# DMI.net
KiCad netlist of a schematic drawn in Altium Designer
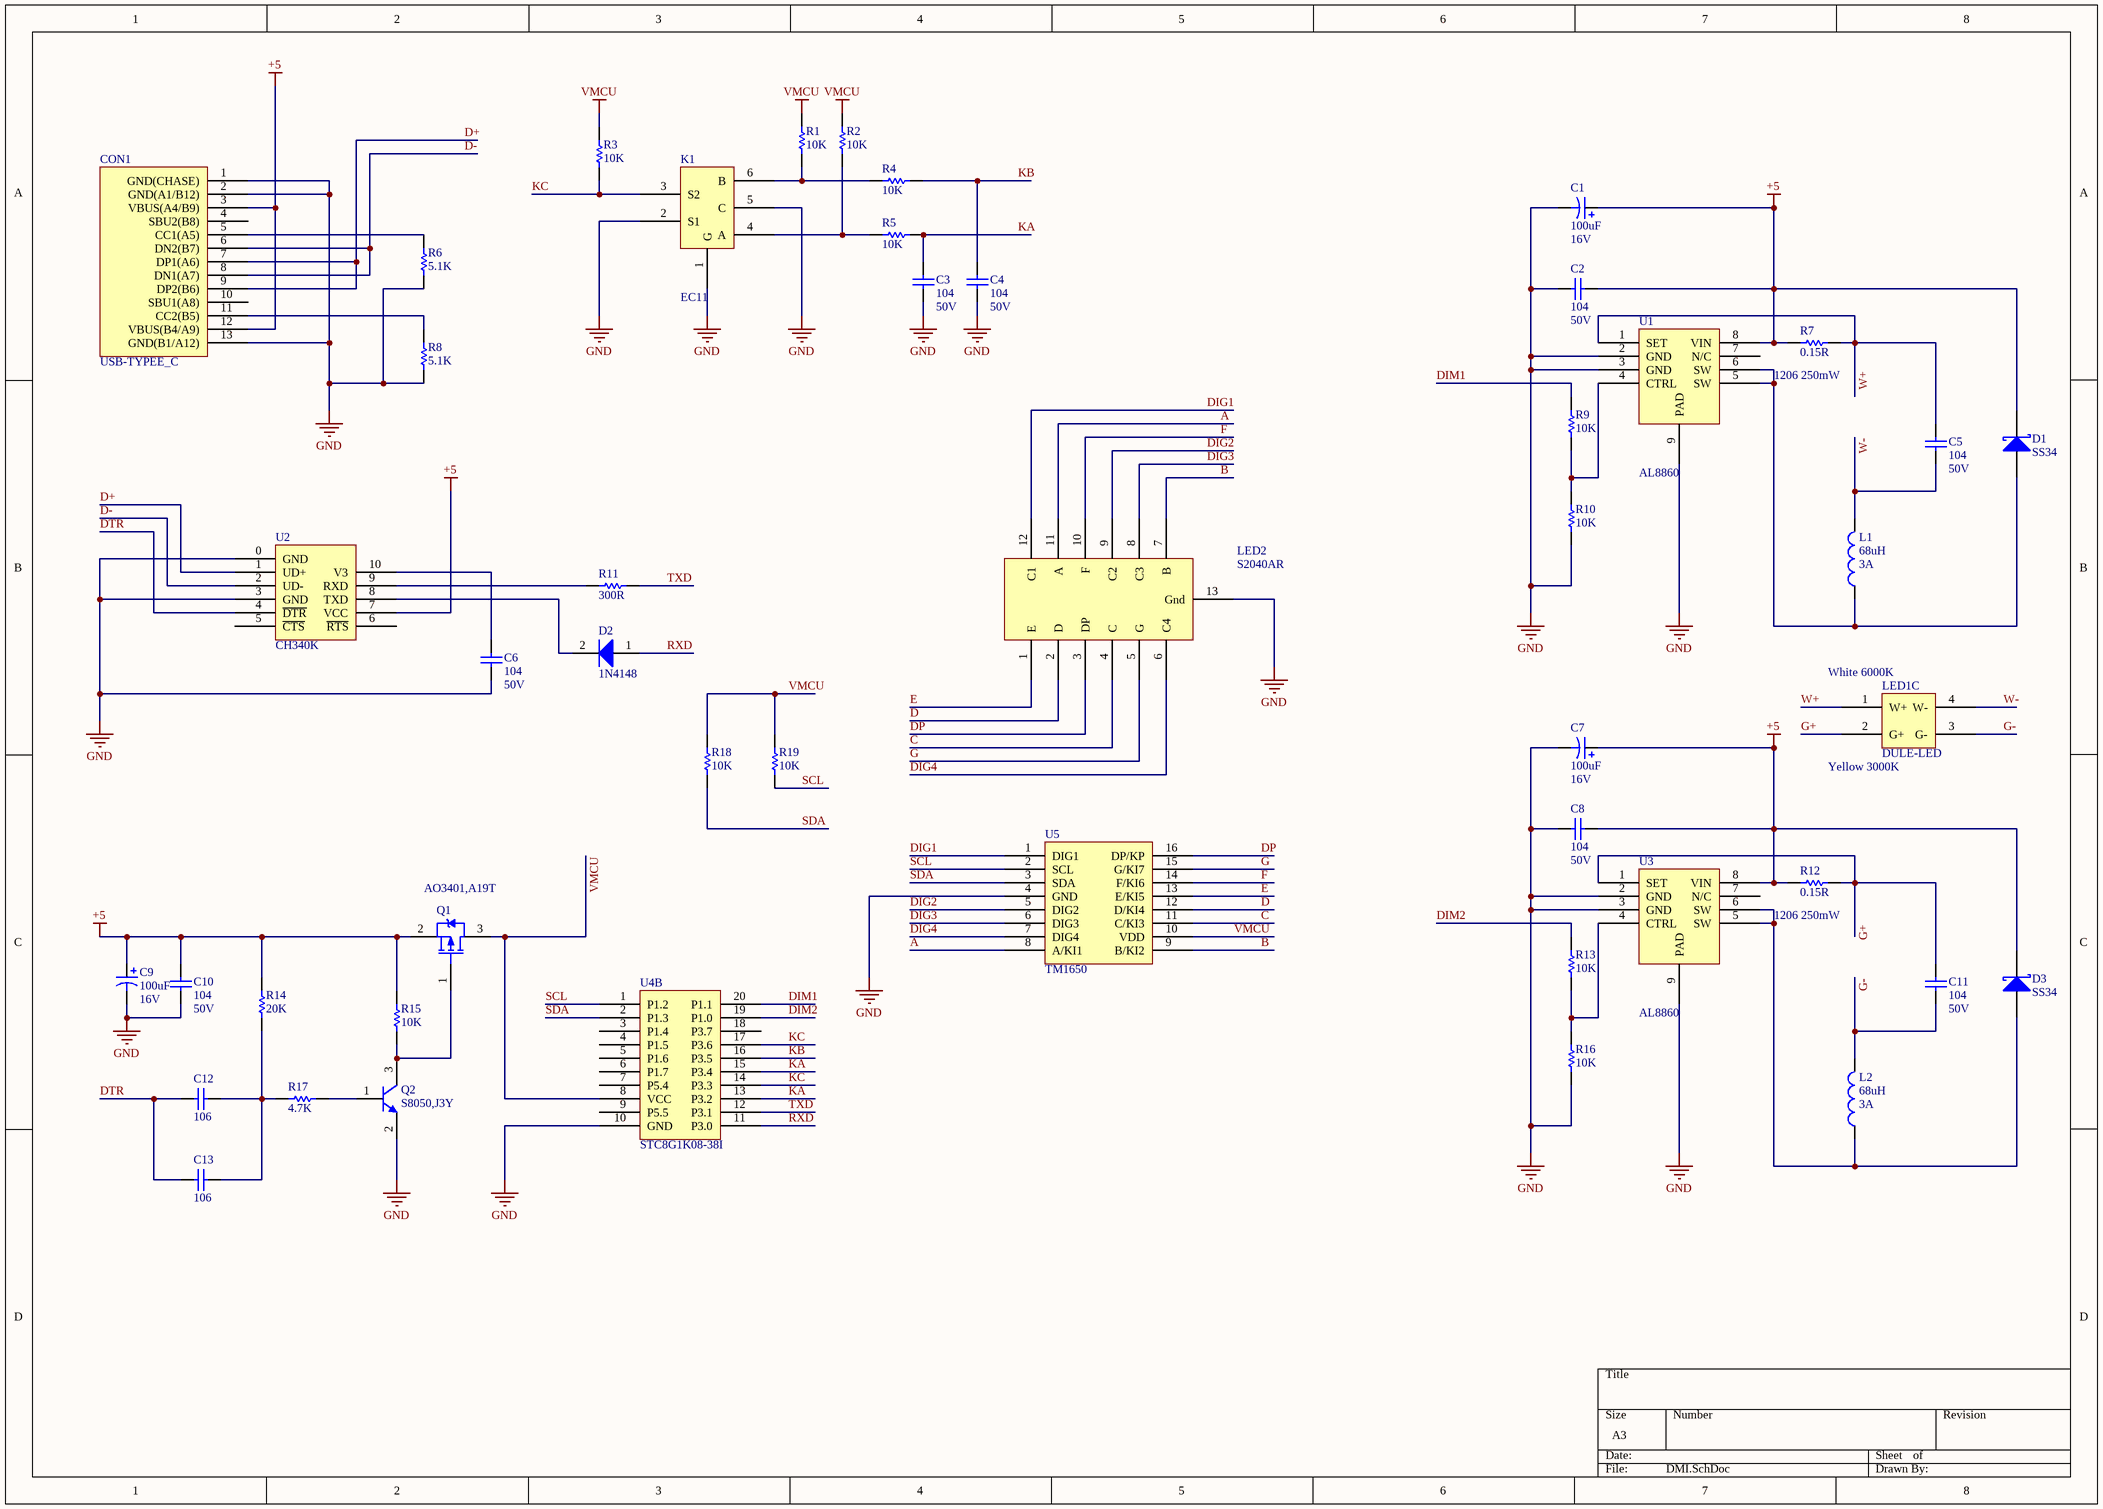
[diagram p0: DMI.SchDoc]

(export (version "E")
  (design (tool "Eeschema 10.0.6"))
  (components
    (comp (ref "C1")
      (value "16V")
      (footprint "DMI:TC6032-2412")
      (description "Polarized Capacitor (Radial)")
      (fields (field (name "ALTIUM_VALUE") "100uF") (field (name "PUBLISHER") "Altium Limited"))
      (libsource (lib "Miscellaneous Devices") (part "Cap Pol1"))
    )
    (comp (ref "C2")
      (value "50V")
      (footprint "DMI:CAPC1608L")
      (description "Capacitor")
      (fields (field (name "ALTIUM_VALUE") "104") (field (name "PUBLISHER") "Altium Limited"))
      (libsource (lib "Miscellaneous Devices") (part "Cap"))
    )
    (comp (ref "C3")
      (value "50V")
      (footprint "DMI:CAPC1608L")
      (description "Capacitor")
      (fields (field (name "ALTIUM_VALUE") "104") (field (name "PUBLISHER") "Altium Limited"))
      (libsource (lib "Miscellaneous Devices") (part "Cap"))
    )
    (comp (ref "C4")
      (value "50V")
      (footprint "DMI:CAPC1608L")
      (description "Capacitor")
      (fields (field (name "ALTIUM_VALUE") "104") (field (name "PUBLISHER") "Altium Limited"))
      (libsource (lib "Miscellaneous Devices") (part "Cap"))
    )
    (comp (ref "C5")
      (value "50V")
      (footprint "DMI:CAPC1608L")
      (description "Capacitor")
      (fields (field (name "ALTIUM_VALUE") "104") (field (name "PUBLISHER") "Altium Limited"))
      (libsource (lib "Miscellaneous Devices") (part "Cap"))
    )
    (comp (ref "C6")
      (value "50V")
      (footprint "DMI:CAPC1608L")
      (description "Capacitor")
      (fields (field (name "ALTIUM_VALUE") "104") (field (name "PUBLISHER") "Altium Limited"))
      (libsource (lib "Miscellaneous Devices") (part "Cap"))
    )
    (comp (ref "C7")
      (value "16V")
      (footprint "DMI:TC6032-2412")
      (description "Polarized Capacitor (Radial)")
      (fields (field (name "ALTIUM_VALUE") "100uF") (field (name "PUBLISHER") "Altium Limited"))
      (libsource (lib "Miscellaneous Devices") (part "Cap Pol1"))
    )
    (comp (ref "C8")
      (value "50V")
      (footprint "DMI:CAPC1608L")
      (description "Capacitor")
      (fields (field (name "ALTIUM_VALUE") "104") (field (name "PUBLISHER") "Altium Limited"))
      (libsource (lib "Miscellaneous Devices") (part "Cap"))
    )
    (comp (ref "C9")
      (value "16V")
      (footprint "DMI:TC6032-2412")
      (description "Polarized Capacitor (Radial)")
      (fields (field (name "ALTIUM_VALUE") "100uF") (field (name "PUBLISHER") "Altium Limited"))
      (libsource (lib "Miscellaneous Devices") (part "Cap Pol1"))
    )
    (comp (ref "C10")
      (value "50V")
      (footprint "DMI:CAPC1608L")
      (description "Capacitor")
      (fields (field (name "ALTIUM_VALUE") "104") (field (name "PUBLISHER") "Altium Limited"))
      (libsource (lib "Miscellaneous Devices") (part "Cap"))
    )
    (comp (ref "C11")
      (value "50V")
      (footprint "DMI:CAPC1608L")
      (description "Capacitor")
      (fields (field (name "ALTIUM_VALUE") "104") (field (name "PUBLISHER") "Altium Limited"))
      (libsource (lib "Miscellaneous Devices") (part "Cap"))
    )
    (comp (ref "C12")
      (value "106")
      (footprint "DMI:CAPC1608L")
      (description "Capacitor")
      (fields (field (name "PUBLISHER") "Altium Limited"))
      (libsource (lib "Miscellaneous Devices") (part "Cap"))
    )
    (comp (ref "C13")
      (value "106")
      (footprint "DMI:CAPC1608L")
      (description "Capacitor")
      (fields (field (name "PUBLISHER") "Altium Limited"))
      (libsource (lib "Miscellaneous Devices") (part "Cap"))
    )
    (comp (ref "CON1")
      (value "USB-TYPEE_C")
      (footprint "DMI:USB-TYPE_C")
      (libsource (lib "DMI") (part "USB-TYPEE_C"))
    )
    (comp (ref "D1")
      (value "SS34")
      (footprint "DMI:DO-214AC")
      (description "Schottky Diode")
      (fields (field (name "PUBLISHER") "Altium Limited"))
      (libsource (lib "Miscellaneous Devices") (part "D Schottky"))
    )
    (comp (ref "D2")
      (value "1N4148")
      (footprint "DMI:CD3216-1206")
      (description "Default Diode")
      (fields (field (name "PUBLISHER") "Altium Limited"))
      (libsource (lib "Miscellaneous Devices") (part "Diode"))
    )
    (comp (ref "D3")
      (value "SS34")
      (footprint "DMI:DO-214AC")
      (description "Schottky Diode")
      (fields (field (name "PUBLISHER") "Altium Limited"))
      (libsource (lib "Miscellaneous Devices") (part "D Schottky"))
    )
    (comp (ref "K1") (value "EC11") (footprint "DMI:EC11") (libsource (lib "DMI") (part "EC11")))
    (comp (ref "L1")
      (value "3A")
      (footprint "DMI:CYH125")
      (description "Inductor")
      (fields (field (name "ALTIUM_VALUE") "68uH") (field (name "PUBLISHER") "Altium Limited"))
      (libsource (lib "Miscellaneous Devices") (part "Inductor"))
    )
    (comp (ref "L2")
      (value "3A")
      (footprint "DMI:CYH125")
      (description "Inductor")
      (fields (field (name "ALTIUM_VALUE") "68uH") (field (name "PUBLISHER") "Altium Limited"))
      (libsource (lib "Miscellaneous Devices") (part "Inductor"))
    )
    (comp (ref "LED1")
      (value "DULE-LED")
      (footprint "DMI:DULE-LED-3W")
      (libsource (lib "DMI") (part "DULE-LED"))
    )
    (comp (ref "LED2") (value "S2040AR") (footprint "DMI:S2040AR") (libsource (lib "DMI") (part "S2040AR")))
    (comp (ref "Q1")
      (value "AO3401,A19T")
      (footprint "DMI:SOT-23B_L")
      (description "P-Channel Power MOSFET")
      (fields (field (name "PUBLISHER") "Altium Limited"))
      (libsource (lib "Miscellaneous Devices") (part "PMOS-2"))
    )
    (comp (ref "Q2")
      (value "S8050,J3Y")
      (footprint "DMI:SOT-23B_L")
      (description "NPN Bipolar Transistor")
      (fields (field (name "PUBLISHER") "Altium Limited"))
      (libsource (lib "Miscellaneous Devices") (part "NPN"))
    )
    (comp (ref "R1")
      (value "10K")
      (footprint "DMI:RESC1608L")
      (description "Resistor")
      (fields (field (name "Comment") "Res1") (field (name "PUBLISHER") "Altium Limited"))
      (libsource (lib "Miscellaneous Devices") (part "Res1"))
    )
    (comp (ref "R2")
      (value "10K")
      (footprint "DMI:RESC1608L")
      (description "Resistor")
      (fields (field (name "Comment") "Res1") (field (name "PUBLISHER") "Altium Limited"))
      (libsource (lib "Miscellaneous Devices") (part "Res1"))
    )
    (comp (ref "R3")
      (value "10K")
      (footprint "DMI:RESC1608L")
      (description "Resistor")
      (fields (field (name "Comment") "Res1") (field (name "PUBLISHER") "Altium Limited"))
      (libsource (lib "Miscellaneous Devices") (part "Res1"))
    )
    (comp (ref "R4")
      (value "10K")
      (footprint "DMI:RESC1608L")
      (description "Resistor")
      (fields (field (name "Comment") "Res1") (field (name "PUBLISHER") "Altium Limited"))
      (libsource (lib "Miscellaneous Devices") (part "Res1"))
    )
    (comp (ref "R5")
      (value "10K")
      (footprint "DMI:RESC1608L")
      (description "Resistor")
      (fields (field (name "Comment") "Res1") (field (name "PUBLISHER") "Altium Limited"))
      (libsource (lib "Miscellaneous Devices") (part "Res1"))
    )
    (comp (ref "R6")
      (value "5.1K")
      (footprint "DMI:RESC1608L")
      (description "Resistor")
      (fields (field (name "Comment") "Res1") (field (name "PUBLISHER") "Altium Limited"))
      (libsource (lib "Miscellaneous Devices") (part "Res1"))
    )
    (comp (ref "R7")
      (value "1206 250mW")
      (footprint "DMI:RESC3216L")
      (description "Resistor")
      (fields (field (name "ALTIUM_VALUE") "0.15R") (field (name "PUBLISHER") "Altium Limited"))
      (libsource (lib "Miscellaneous Devices") (part "Res1"))
    )
    (comp (ref "R8")
      (value "5.1K")
      (footprint "DMI:RESC1608L")
      (description "Resistor")
      (fields (field (name "Comment") "Res1") (field (name "PUBLISHER") "Altium Limited"))
      (libsource (lib "Miscellaneous Devices") (part "Res1"))
    )
    (comp (ref "R9")
      (value "10K")
      (footprint "DMI:RESC1608L")
      (description "Resistor")
      (fields (field (name "Comment") "Res1") (field (name "PUBLISHER") "Altium Limited"))
      (libsource (lib "Miscellaneous Devices") (part "Res1"))
    )
    (comp (ref "R10")
      (value "10K")
      (footprint "DMI:RESC1608L")
      (description "Resistor")
      (fields (field (name "Comment") "Res1") (field (name "PUBLISHER") "Altium Limited"))
      (libsource (lib "Miscellaneous Devices") (part "Res1"))
    )
    (comp (ref "R11")
      (value "300R")
      (footprint "DMI:RESC1608L")
      (description "Resistor")
      (fields (field (name "Comment") "Res1") (field (name "PUBLISHER") "Altium Limited"))
      (libsource (lib "Miscellaneous Devices") (part "Res1"))
    )
    (comp (ref "R12")
      (value "1206 250mW")
      (footprint "DMI:RESC3216L")
      (description "Resistor")
      (fields (field (name "ALTIUM_VALUE") "0.15R") (field (name "PUBLISHER") "Altium Limited"))
      (libsource (lib "Miscellaneous Devices") (part "Res1"))
    )
    (comp (ref "R13")
      (value "10K")
      (footprint "DMI:RESC1608L")
      (description "Resistor")
      (fields (field (name "Comment") "Res1") (field (name "PUBLISHER") "Altium Limited"))
      (libsource (lib "Miscellaneous Devices") (part "Res1"))
    )
    (comp (ref "R14")
      (value "20K")
      (footprint "DMI:RESC1608L")
      (description "Resistor")
      (fields (field (name "Comment") "Res1") (field (name "PUBLISHER") "Altium Limited"))
      (libsource (lib "Miscellaneous Devices") (part "Res1"))
    )
    (comp (ref "R15")
      (value "10K")
      (footprint "DMI:RESC1608L")
      (description "Resistor")
      (fields (field (name "Comment") "Res1") (field (name "PUBLISHER") "Altium Limited"))
      (libsource (lib "Miscellaneous Devices") (part "Res1"))
    )
    (comp (ref "R16")
      (value "10K")
      (footprint "DMI:RESC1608L")
      (description "Resistor")
      (fields (field (name "Comment") "Res1") (field (name "PUBLISHER") "Altium Limited"))
      (libsource (lib "Miscellaneous Devices") (part "Res1"))
    )
    (comp (ref "R17")
      (value "4.7K")
      (footprint "DMI:RESC1608L")
      (description "Resistor")
      (fields (field (name "Comment") "Res1") (field (name "PUBLISHER") "Altium Limited"))
      (libsource (lib "Miscellaneous Devices") (part "Res1"))
    )
    (comp (ref "R18")
      (value "10K")
      (footprint "DMI:RESC1608L")
      (description "Resistor")
      (fields (field (name "Comment") "Res1") (field (name "PUBLISHER") "Altium Limited"))
      (libsource (lib "Miscellaneous Devices") (part "Res1"))
    )
    (comp (ref "R19")
      (value "10K")
      (footprint "DMI:RESC1608L")
      (description "Resistor")
      (fields (field (name "Comment") "Res1") (field (name "PUBLISHER") "Altium Limited"))
      (libsource (lib "Miscellaneous Devices") (part "Res1"))
    )
    (comp (ref "U1")
      (value "AL8860")
      (footprint "DMI:TSOP65P490_HS-8N")
      (libsource (lib "DMI") (part "AL8860"))
    )
    (comp (ref "U2")
      (value "CH340K")
      (footprint "DMI:ESOP100-10")
      (libsource (lib "FireFly") (part "CH340K"))
    )
    (comp (ref "U3")
      (value "AL8860")
      (footprint "DMI:TSOP65P490_HS-8N")
      (libsource (lib "DMI") (part "AL8860"))
    )
    (comp (ref "U4")
      (value "STC8G1K08-38I")
      (footprint "DMI:TSOP65P640-20BL")
      (libsource (lib "DMI") (part "STC8G1K08-38I"))
    )
    (comp (ref "U5")
      (value "TM1650")
      (footprint "DMI:SOP127P762-16L")
      (libsource (lib "DMI") (part "TM1650"))
    )
  )
  (nets
    (net (code "1") (name "+5") (class "Default")
      (node (ref "C1") (pin "1") (pinfunction "1_1") (pintype "passive"))
      (node (ref "C10") (pin "2") (pinfunction "2_2") (pintype "passive"))
      (node (ref "C2") (pin "2") (pinfunction "2_2") (pintype "passive"))
      (node (ref "C7") (pin "1") (pinfunction "1_1") (pintype "passive"))
      (node (ref "C8") (pin "2") (pinfunction "2_2") (pintype "passive"))
      (node (ref "C9") (pin "1") (pinfunction "1_1") (pintype "passive"))
      (node (ref "CON1") (pin "12") (pinfunction "VBUS(B4/A9)_12") (pintype "passive"))
      (node (ref "CON1") (pin "3") (pinfunction "VBUS(A4/B9)_3") (pintype "passive"))
      (node (ref "D1") (pin "2") (pinfunction "K_2") (pintype "passive"))
      (node (ref "D3") (pin "2") (pinfunction "K_2") (pintype "passive"))
      (node (ref "Q1") (pin "2") (pinfunction "S_2") (pintype "passive"))
      (node (ref "R12") (pin "2") (pinfunction "2_2") (pintype "passive"))
      (node (ref "R14") (pin "1") (pinfunction "1_1") (pintype "passive"))
      (node (ref "R15") (pin "2") (pinfunction "2_2") (pintype "passive"))
      (node (ref "R7") (pin "2") (pinfunction "2_2") (pintype "passive"))
      (node (ref "U1") (pin "8") (pinfunction "VIN_8") (pintype "passive"))
      (node (ref "U2") (pin "7") (pinfunction "VCC_7") (pintype "passive"))
      (node (ref "U3") (pin "8") (pinfunction "VIN_8") (pintype "passive"))
    )
    (net (code "2") (name "/A") (class "Default")
      (node (ref "LED2") (pin "11") (pinfunction "A_11") (pintype "passive"))
      (node (ref "U5") (pin "8") (pinfunction "A/KI1_8") (pintype "passive"))
    )
    (net (code "3") (name "/B") (class "Default")
      (node (ref "LED2") (pin "7") (pinfunction "B_7") (pintype "passive"))
      (node (ref "U5") (pin "9") (pinfunction "B/KI2_9") (pintype "passive"))
    )
    (net (code "4") (name "/C") (class "Default")
      (node (ref "LED2") (pin "4") (pinfunction "C_4") (pintype "passive"))
      (node (ref "U5") (pin "11") (pinfunction "C/KI3_11") (pintype "passive"))
    )
    (net (code "5") (name "/D") (class "Default")
      (node (ref "LED2") (pin "2") (pinfunction "D_2") (pintype "passive"))
      (node (ref "U5") (pin "12") (pinfunction "D/KI4_12") (pintype "passive"))
    )
    (net (code "6") (name "/D+") (class "Default")
      (node (ref "CON1") (pin "7") (pinfunction "DP1(A6)_7") (pintype "passive"))
      (node (ref "CON1") (pin "9") (pinfunction "DP2(B6)_9") (pintype "passive"))
      (node (ref "U2") (pin "1") (pinfunction "UD+_1") (pintype "passive"))
    )
    (net (code "7") (name "/D-") (class "Default")
      (node (ref "CON1") (pin "6") (pinfunction "DN2(B7)_6") (pintype "passive"))
      (node (ref "CON1") (pin "8") (pinfunction "DN1(A7)_8") (pintype "passive"))
      (node (ref "U2") (pin "2") (pinfunction "UD-_2") (pintype "passive"))
    )
    (net (code "8") (name "/DIG1") (class "Default")
      (node (ref "LED2") (pin "12") (pinfunction "C1_12") (pintype "passive"))
      (node (ref "U5") (pin "1") (pinfunction "DIG1_1") (pintype "passive"))
    )
    (net (code "9") (name "/DIG2") (class "Default")
      (node (ref "LED2") (pin "9") (pinfunction "C2_9") (pintype "passive"))
      (node (ref "U5") (pin "5") (pinfunction "DIG2_5") (pintype "passive"))
    )
    (net (code "10") (name "/DIG3") (class "Default")
      (node (ref "LED2") (pin "8") (pinfunction "C3_8") (pintype "passive"))
      (node (ref "U5") (pin "6") (pinfunction "DIG3_6") (pintype "passive"))
    )
    (net (code "11") (name "/DIG4") (class "Default")
      (node (ref "LED2") (pin "6") (pinfunction "C4_6") (pintype "passive"))
      (node (ref "U5") (pin "7") (pinfunction "DIG4_7") (pintype "passive"))
    )
    (net (code "12") (name "/DIM1") (class "Default")
      (node (ref "R9") (pin "1") (pinfunction "1_1") (pintype "passive"))
      (node (ref "U4") (pin "20") (pinfunction "P1.1_20") (pintype "passive"))
    )
    (net (code "13") (name "/DIM2") (class "Default")
      (node (ref "R13") (pin "1") (pinfunction "1_1") (pintype "passive"))
      (node (ref "U4") (pin "19") (pinfunction "P1.0_19") (pintype "passive"))
    )
    (net (code "14") (name "/DP") (class "Default")
      (node (ref "LED2") (pin "3") (pinfunction "DP_3") (pintype "passive"))
      (node (ref "U5") (pin "16") (pinfunction "DP/KP_16") (pintype "passive"))
    )
    (net (code "15") (name "/DTR") (class "Default")
      (node (ref "C12") (pin "2") (pinfunction "2_2") (pintype "passive"))
      (node (ref "C13") (pin "2") (pinfunction "2_2") (pintype "passive"))
      (node (ref "U2") (pin "4") (pinfunction "~{DTR}_4") (pintype "passive"))
    )
    (net (code "16") (name "/E") (class "Default")
      (node (ref "LED2") (pin "1") (pinfunction "E_1") (pintype "passive"))
      (node (ref "U5") (pin "13") (pinfunction "E/KI5_13") (pintype "passive"))
    )
    (net (code "17") (name "/F") (class "Default")
      (node (ref "LED2") (pin "10") (pinfunction "F_10") (pintype "passive"))
      (node (ref "U5") (pin "14") (pinfunction "F/KI6_14") (pintype "passive"))
    )
    (net (code "18") (name "/G") (class "Default")
      (node (ref "LED2") (pin "5") (pinfunction "G_5") (pintype "passive"))
      (node (ref "U5") (pin "15") (pinfunction "G/KI7_15") (pintype "passive"))
    )
    (net (code "19") (name "/G+") (class "Default")
      (node (ref "C11") (pin "2") (pinfunction "2_2") (pintype "passive"))
      (node (ref "LED1") (pin "2") (pinfunction "G+_2") (pintype "passive"))
      (node (ref "R12") (pin "1") (pinfunction "1_1") (pintype "passive"))
      (node (ref "U3") (pin "1") (pinfunction "SET_1") (pintype "passive"))
    )
    (net (code "20") (name "/G-") (class "Default")
      (node (ref "C11") (pin "1") (pinfunction "1_1") (pintype "passive"))
      (node (ref "L2") (pin "2") (pinfunction "2_2") (pintype "passive"))
      (node (ref "LED1") (pin "3") (pinfunction "G-_3") (pintype "passive"))
    )
    (net (code "21") (name "/KA") (class "Default")
      (node (ref "C3") (pin "2") (pinfunction "2_2") (pintype "passive"))
      (node (ref "R5") (pin "2") (pinfunction "2_2") (pintype "passive"))
      (node (ref "U4") (pin "13") (pinfunction "P3.2_13") (pintype "passive"))
      (node (ref "U4") (pin "15") (pinfunction "P3.4_15") (pintype "passive"))
    )
    (net (code "22") (name "/KB") (class "Default")
      (node (ref "C4") (pin "2") (pinfunction "2_2") (pintype "passive"))
      (node (ref "R4") (pin "2") (pinfunction "2_2") (pintype "passive"))
      (node (ref "U4") (pin "16") (pinfunction "P3.5_16") (pintype "passive"))
    )
    (net (code "23") (name "/KC") (class "Default")
      (node (ref "K1") (pin "3") (pinfunction "S2_3") (pintype "passive"))
      (node (ref "R3") (pin "2") (pinfunction "2_2") (pintype "passive"))
      (node (ref "U4") (pin "14") (pinfunction "P3.3_14") (pintype "passive"))
      (node (ref "U4") (pin "17") (pinfunction "P3.6_17") (pintype "passive"))
    )
    (net (code "24") (name "/RXD") (class "Default")
      (node (ref "D2") (pin "1") (pinfunction "A_1") (pintype "passive"))
      (node (ref "U4") (pin "11") (pinfunction "P3.0_11") (pintype "passive"))
    )
    (net (code "25") (name "/SCL") (class "Default")
      (node (ref "R19") (pin "1") (pinfunction "1_1") (pintype "passive"))
      (node (ref "U4") (pin "1") (pinfunction "P1.2_1") (pintype "passive"))
      (node (ref "U5") (pin "2") (pinfunction "SCL_2") (pintype "passive"))
    )
    (net (code "26") (name "/SDA") (class "Default")
      (node (ref "R18") (pin "1") (pinfunction "1_1") (pintype "passive"))
      (node (ref "U4") (pin "2") (pinfunction "P1.3_2") (pintype "passive"))
      (node (ref "U5") (pin "3") (pinfunction "SDA_3") (pintype "passive"))
    )
    (net (code "27") (name "/TXD") (class "Default")
      (node (ref "R11") (pin "2") (pinfunction "2_2") (pintype "passive"))
      (node (ref "U4") (pin "12") (pinfunction "P3.1_12") (pintype "passive"))
    )
    (net (code "28") (name "/W+") (class "Default")
      (node (ref "C5") (pin "2") (pinfunction "2_2") (pintype "passive"))
      (node (ref "LED1") (pin "1") (pinfunction "W+_1") (pintype "passive"))
      (node (ref "R7") (pin "1") (pinfunction "1_1") (pintype "passive"))
      (node (ref "U1") (pin "1") (pinfunction "SET_1") (pintype "passive"))
    )
    (net (code "29") (name "/W-") (class "Default")
      (node (ref "C5") (pin "1") (pinfunction "1_1") (pintype "passive"))
      (node (ref "L1") (pin "2") (pinfunction "2_2") (pintype "passive"))
      (node (ref "LED1") (pin "4") (pinfunction "W-_4") (pintype "passive"))
    )
    (net (code "30") (name "GND") (class "Default")
      (node (ref "C1") (pin "2") (pinfunction "2_2") (pintype "passive"))
      (node (ref "C10") (pin "1") (pinfunction "1_1") (pintype "passive"))
      (node (ref "C2") (pin "1") (pinfunction "1_1") (pintype "passive"))
      (node (ref "C3") (pin "1") (pinfunction "1_1") (pintype "passive"))
      (node (ref "C4") (pin "1") (pinfunction "1_1") (pintype "passive"))
      (node (ref "C6") (pin "1") (pinfunction "1_1") (pintype "passive"))
      (node (ref "C7") (pin "2") (pinfunction "2_2") (pintype "passive"))
      (node (ref "C8") (pin "1") (pinfunction "1_1") (pintype "passive"))
      (node (ref "C9") (pin "2") (pinfunction "2_2") (pintype "passive"))
      (node (ref "CON1") (pin "1") (pinfunction "GND(CHASE)_1") (pintype "passive"))
      (node (ref "CON1") (pin "13") (pinfunction "GND(B1/A12)_13") (pintype "passive"))
      (node (ref "CON1") (pin "2") (pinfunction "GND(A1/B12)_2") (pintype "passive"))
      (node (ref "K1") (pin "1") (pinfunction "G_1") (pintype "passive"))
      (node (ref "K1") (pin "2") (pinfunction "S1_2") (pintype "passive"))
      (node (ref "K1") (pin "5") (pinfunction "C_5") (pintype "passive"))
      (node (ref "LED2") (pin "13") (pinfunction "Gnd_13") (pintype "passive"))
      (node (ref "Q2") (pin "2") (pinfunction "E_2") (pintype "passive"))
      (node (ref "R10") (pin "2") (pinfunction "2_2") (pintype "passive"))
      (node (ref "R16") (pin "2") (pinfunction "2_2") (pintype "passive"))
      (node (ref "R6") (pin "2") (pinfunction "2_2") (pintype "passive"))
      (node (ref "R8") (pin "2") (pinfunction "2_2") (pintype "passive"))
      (node (ref "U1") (pin "2") (pinfunction "GND_2") (pintype "passive"))
      (node (ref "U1") (pin "3") (pinfunction "GND_3") (pintype "passive"))
      (node (ref "U1") (pin "9") (pinfunction "PAD_9") (pintype "passive"))
      (node (ref "U2") (pin "0") (pinfunction "GND_0") (pintype "passive"))
      (node (ref "U2") (pin "3") (pinfunction "GND_3") (pintype "passive"))
      (node (ref "U3") (pin "2") (pinfunction "GND_2") (pintype "passive"))
      (node (ref "U3") (pin "3") (pinfunction "GND_3") (pintype "passive"))
      (node (ref "U3") (pin "9") (pinfunction "PAD_9") (pintype "passive"))
      (node (ref "U4") (pin "10") (pinfunction "GND_10") (pintype "passive"))
      (node (ref "U5") (pin "4") (pinfunction "GND_4") (pintype "passive"))
    )
    (net (code "31") (name "Net-(C12-Pad1)") (class "Default")
      (node (ref "C12") (pin "1") (pinfunction "1_1") (pintype "passive"))
      (node (ref "C13") (pin "1") (pinfunction "1_1") (pintype "passive"))
      (node (ref "R14") (pin "2") (pinfunction "2_2") (pintype "passive"))
      (node (ref "R17") (pin "2") (pinfunction "2_2") (pintype "passive"))
    )
    (net (code "32") (name "Net-(CON1-CC1(A5))") (class "Default")
      (node (ref "CON1") (pin "5") (pinfunction "CC1(A5)_5") (pintype "passive"))
      (node (ref "R6") (pin "1") (pinfunction "1_1") (pintype "passive"))
    )
    (net (code "33") (name "Net-(CON1-CC2(B5))") (class "Default")
      (node (ref "CON1") (pin "11") (pinfunction "CC2(B5)_11") (pintype "passive"))
      (node (ref "R8") (pin "1") (pinfunction "1_1") (pintype "passive"))
    )
    (net (code "34") (name "Net-(D1-A)") (class "Default")
      (node (ref "D1") (pin "1") (pinfunction "A_1") (pintype "passive"))
      (node (ref "L1") (pin "1") (pinfunction "1_1") (pintype "passive"))
      (node (ref "U1") (pin "5") (pinfunction "SW_5") (pintype "passive"))
      (node (ref "U1") (pin "6") (pinfunction "SW_6") (pintype "passive"))
    )
    (net (code "35") (name "Net-(D2-K)") (class "Default")
      (node (ref "D2") (pin "2") (pinfunction "K_2") (pintype "passive"))
      (node (ref "U2") (pin "8") (pinfunction "TXD_8") (pintype "passive"))
    )
    (net (code "36") (name "Net-(D3-A)") (class "Default")
      (node (ref "D3") (pin "1") (pinfunction "A_1") (pintype "passive"))
      (node (ref "L2") (pin "1") (pinfunction "1_1") (pintype "passive"))
      (node (ref "U3") (pin "5") (pinfunction "SW_5") (pintype "passive"))
      (node (ref "U3") (pin "6") (pinfunction "SW_6") (pintype "passive"))
    )
    (net (code "37") (name "Net-(K1-A)") (class "Default")
      (node (ref "K1") (pin "4") (pinfunction "A_4") (pintype "passive"))
      (node (ref "R2") (pin "2") (pinfunction "2_2") (pintype "passive"))
      (node (ref "R5") (pin "1") (pinfunction "1_1") (pintype "passive"))
    )
    (net (code "38") (name "Net-(K1-B)") (class "Default")
      (node (ref "K1") (pin "6") (pinfunction "B_6") (pintype "passive"))
      (node (ref "R1") (pin "2") (pinfunction "2_2") (pintype "passive"))
      (node (ref "R4") (pin "1") (pinfunction "1_1") (pintype "passive"))
    )
    (net (code "39") (name "Net-(Q1-G)") (class "Default")
      (node (ref "Q1") (pin "1") (pinfunction "G_1") (pintype "passive"))
      (node (ref "Q2") (pin "3") (pinfunction "C_3") (pintype "passive"))
      (node (ref "R15") (pin "1") (pinfunction "1_1") (pintype "passive"))
    )
    (net (code "40") (name "Net-(Q2-B)") (class "Default")
      (node (ref "Q2") (pin "1") (pinfunction "B_1") (pintype "passive"))
      (node (ref "R17") (pin "1") (pinfunction "1_1") (pintype "passive"))
    )
    (net (code "41") (name "Net-(U1-CTRL)") (class "Default")
      (node (ref "R10") (pin "1") (pinfunction "1_1") (pintype "passive"))
      (node (ref "R9") (pin "2") (pinfunction "2_2") (pintype "passive"))
      (node (ref "U1") (pin "4") (pinfunction "CTRL_4") (pintype "passive"))
    )
    (net (code "42") (name "Net-(U2-RXD)") (class "Default")
      (node (ref "R11") (pin "1") (pinfunction "1_1") (pintype "passive"))
      (node (ref "U2") (pin "9") (pinfunction "RXD_9") (pintype "passive"))
    )
    (net (code "43") (name "Net-(U2-V3)") (class "Default")
      (node (ref "C6") (pin "2") (pinfunction "2_2") (pintype "passive"))
      (node (ref "U2") (pin "10") (pinfunction "V3_10") (pintype "passive"))
    )
    (net (code "44") (name "Net-(U3-CTRL)") (class "Default")
      (node (ref "R13") (pin "2") (pinfunction "2_2") (pintype "passive"))
      (node (ref "R16") (pin "1") (pinfunction "1_1") (pintype "passive"))
      (node (ref "U3") (pin "4") (pinfunction "CTRL_4") (pintype "passive"))
    )
    (net (code "45") (name "VMCU") (class "Default")
      (node (ref "Q1") (pin "3") (pinfunction "D_3") (pintype "passive"))
      (node (ref "R1") (pin "1") (pinfunction "1_1") (pintype "passive"))
      (node (ref "R18") (pin "2") (pinfunction "2_2") (pintype "passive"))
      (node (ref "R19") (pin "2") (pinfunction "2_2") (pintype "passive"))
      (node (ref "R2") (pin "1") (pinfunction "1_1") (pintype "passive"))
      (node (ref "R3") (pin "1") (pinfunction "1_1") (pintype "passive"))
      (node (ref "U4") (pin "8") (pinfunction "VCC_8") (pintype "passive"))
      (node (ref "U5") (pin "10") (pinfunction "VDD_10") (pintype "passive"))
    )
    (net (code "46") (name "unconnected-(CON1-SBU1(A8)-Pad10)") (class "Default")
      (node (ref "CON1") (pin "10") (pinfunction "SBU1(A8)_10") (pintype "passive"))
    )
    (net (code "47") (name "unconnected-(CON1-SBU2(B8)-Pad4)") (class "Default")
      (node (ref "CON1") (pin "4") (pinfunction "SBU2(B8)_4") (pintype "passive"))
    )
    (net (code "48") (name "unconnected-(U1-N{slash}C-Pad7)") (class "Default")
      (node (ref "U1") (pin "7") (pinfunction "N/C_7") (pintype "passive"))
    )
    (net (code "49") (name "unconnected-(U2-~{CTS}-Pad5)") (class "Default")
      (node (ref "U2") (pin "5") (pinfunction "~{CTS}_5") (pintype "passive"))
    )
    (net (code "50") (name "unconnected-(U2-~{RTS}-Pad6)") (class "Default")
      (node (ref "U2") (pin "6") (pinfunction "~{RTS}_6") (pintype "passive"))
    )
    (net (code "51") (name "unconnected-(U3-N{slash}C-Pad7)") (class "Default")
      (node (ref "U3") (pin "7") (pinfunction "N/C_7") (pintype "passive"))
    )
    (net (code "52") (name "unconnected-(U4B-P1.4-Pad3)") (class "Default")
      (node (ref "U4") (pin "3") (pinfunction "P1.4_3") (pintype "passive"))
    )
    (net (code "53") (name "unconnected-(U4B-P1.5-Pad4)") (class "Default")
      (node (ref "U4") (pin "4") (pinfunction "P1.5_4") (pintype "passive"))
    )
    (net (code "54") (name "unconnected-(U4B-P1.6-Pad5)") (class "Default")
      (node (ref "U4") (pin "5") (pinfunction "P1.6_5") (pintype "passive"))
    )
    (net (code "55") (name "unconnected-(U4B-P1.7-Pad6)") (class "Default")
      (node (ref "U4") (pin "6") (pinfunction "P1.7_6") (pintype "passive"))
    )
    (net (code "56") (name "unconnected-(U4B-P3.7-Pad18)") (class "Default")
      (node (ref "U4") (pin "18") (pinfunction "P3.7_18") (pintype "passive"))
    )
    (net (code "57") (name "unconnected-(U4B-P5.4-Pad7)") (class "Default")
      (node (ref "U4") (pin "7") (pinfunction "P5.4_7") (pintype "passive"))
    )
    (net (code "58") (name "unconnected-(U4B-P5.5-Pad9)") (class "Default")
      (node (ref "U4") (pin "9") (pinfunction "P5.5_9") (pintype "passive"))
    )
  )
)
